# RC_Inverter.net
KiCad netlist of a schematic drawn in Altium Designer
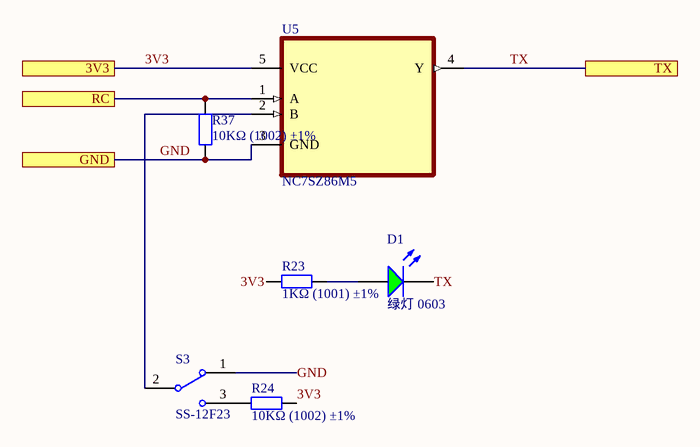
[diagram p0: RC_Inverter.SchDoc]

(export (version "E")
  (design (tool "Eeschema 10.0.6"))
  (components
    (comp (ref "D1")
      (value "绿灯 0603")
      (footprint "0603_LED_S1")
      (description "发光二极管")
      (libsource (lib "Miscellaneous Devices LC") (part "0603 绿灯"))
    )
    (comp (ref "R23")
      (value "1KΩ (1001) ±1%")
      (footprint "0402_R")
      (description "贴片电阻")
      (libsource (lib "Miscellaneous Devices LC") (part "0402 1KΩ (1001) 1%"))
    )
    (comp (ref "R24")
      (value "10KΩ (1002) ±1%")
      (footprint "0402_R")
      (description "贴片电阻")
      (libsource (lib "Miscellaneous Devices LC") (part "0402 10KΩ (1002) 1%"))
    )
    (comp (ref "R37")
      (value "10KΩ (1002) ±1%")
      (footprint "0402_R")
      (description "贴片电阻")
      (libsource (lib "") (part "0402 10KΩ (1002) 1%_1"))
    )
    (comp (ref "S3")
      (value "SS-12F23")
      (footprint "MSK-12C01-07")
      (description "1路波动开关")
      (fields (field (name "版权归属") "源创客"))
      (libsource (lib "5.1   - 按键-开关") (part "SSW-1P"))
    )
    (comp (ref "U5")
      (value "NC7SZ86M5")
      (footprint "SOT95P280X145-5N")
      (description "XOR _Exclusive OR_ IC 1 Channel SOT-23-5")
      (fields (field (name "MF") "ON Semiconductor"))
      (libsource (lib "NC7SZ86M5") (part "NC7SZ86M5"))
    )
  )
  (nets
    (net (code "1") (name "/3V3") (class "Default")
      (node (ref "R23") (pin "1") (pinfunction "1_1") (pintype "passive"))
      (node (ref "R24") (pin "2") (pinfunction "2_2") (pintype "passive"))
      (node (ref "U5") (pin "5") (pinfunction "VCC_5") (pintype "power_in"))
    )
    (net (code "2") (name "/GND") (class "Default")
      (node (ref "R37") (pin "2") (pinfunction "2_2") (pintype "passive"))
      (node (ref "S3") (pin "1") (pinfunction "1_1") (pintype "passive"))
      (node (ref "U5") (pin "3") (pinfunction "GND_3") (pintype "passive"))
    )
    (net (code "3") (name "/RC") (class "Default")
      (node (ref "R37") (pin "1") (pinfunction "1_1") (pintype "passive"))
      (node (ref "U5") (pin "1") (pinfunction "A_1") (pintype "input"))
    )
    (net (code "4") (name "/TX") (class "Default")
      (node (ref "D1") (pin "K") (pinfunction "K_K") (pintype "passive"))
      (node (ref "U5") (pin "4") (pinfunction "Y_4") (pintype "output"))
    )
    (net (code "5") (name "Net-(D1-PadA)") (class "Default")
      (node (ref "D1") (pin "A") (pinfunction "A_A") (pintype "passive"))
      (node (ref "R23") (pin "2") (pinfunction "2_2") (pintype "passive"))
    )
    (net (code "6") (name "Net-(R24-Pad1)") (class "Default")
      (node (ref "R24") (pin "1") (pinfunction "1_1") (pintype "passive"))
      (node (ref "S3") (pin "3") (pinfunction "3_3") (pintype "passive"))
    )
    (net (code "7") (name "Net-(U5-B)") (class "Default")
      (node (ref "S3") (pin "2") (pinfunction "2_2") (pintype "passive"))
      (node (ref "U5") (pin "2") (pinfunction "B_2") (pintype "input"))
    )
  )
)
